# 4AND_1.net
KiCad netlist of a schematic drawn in EAGLE
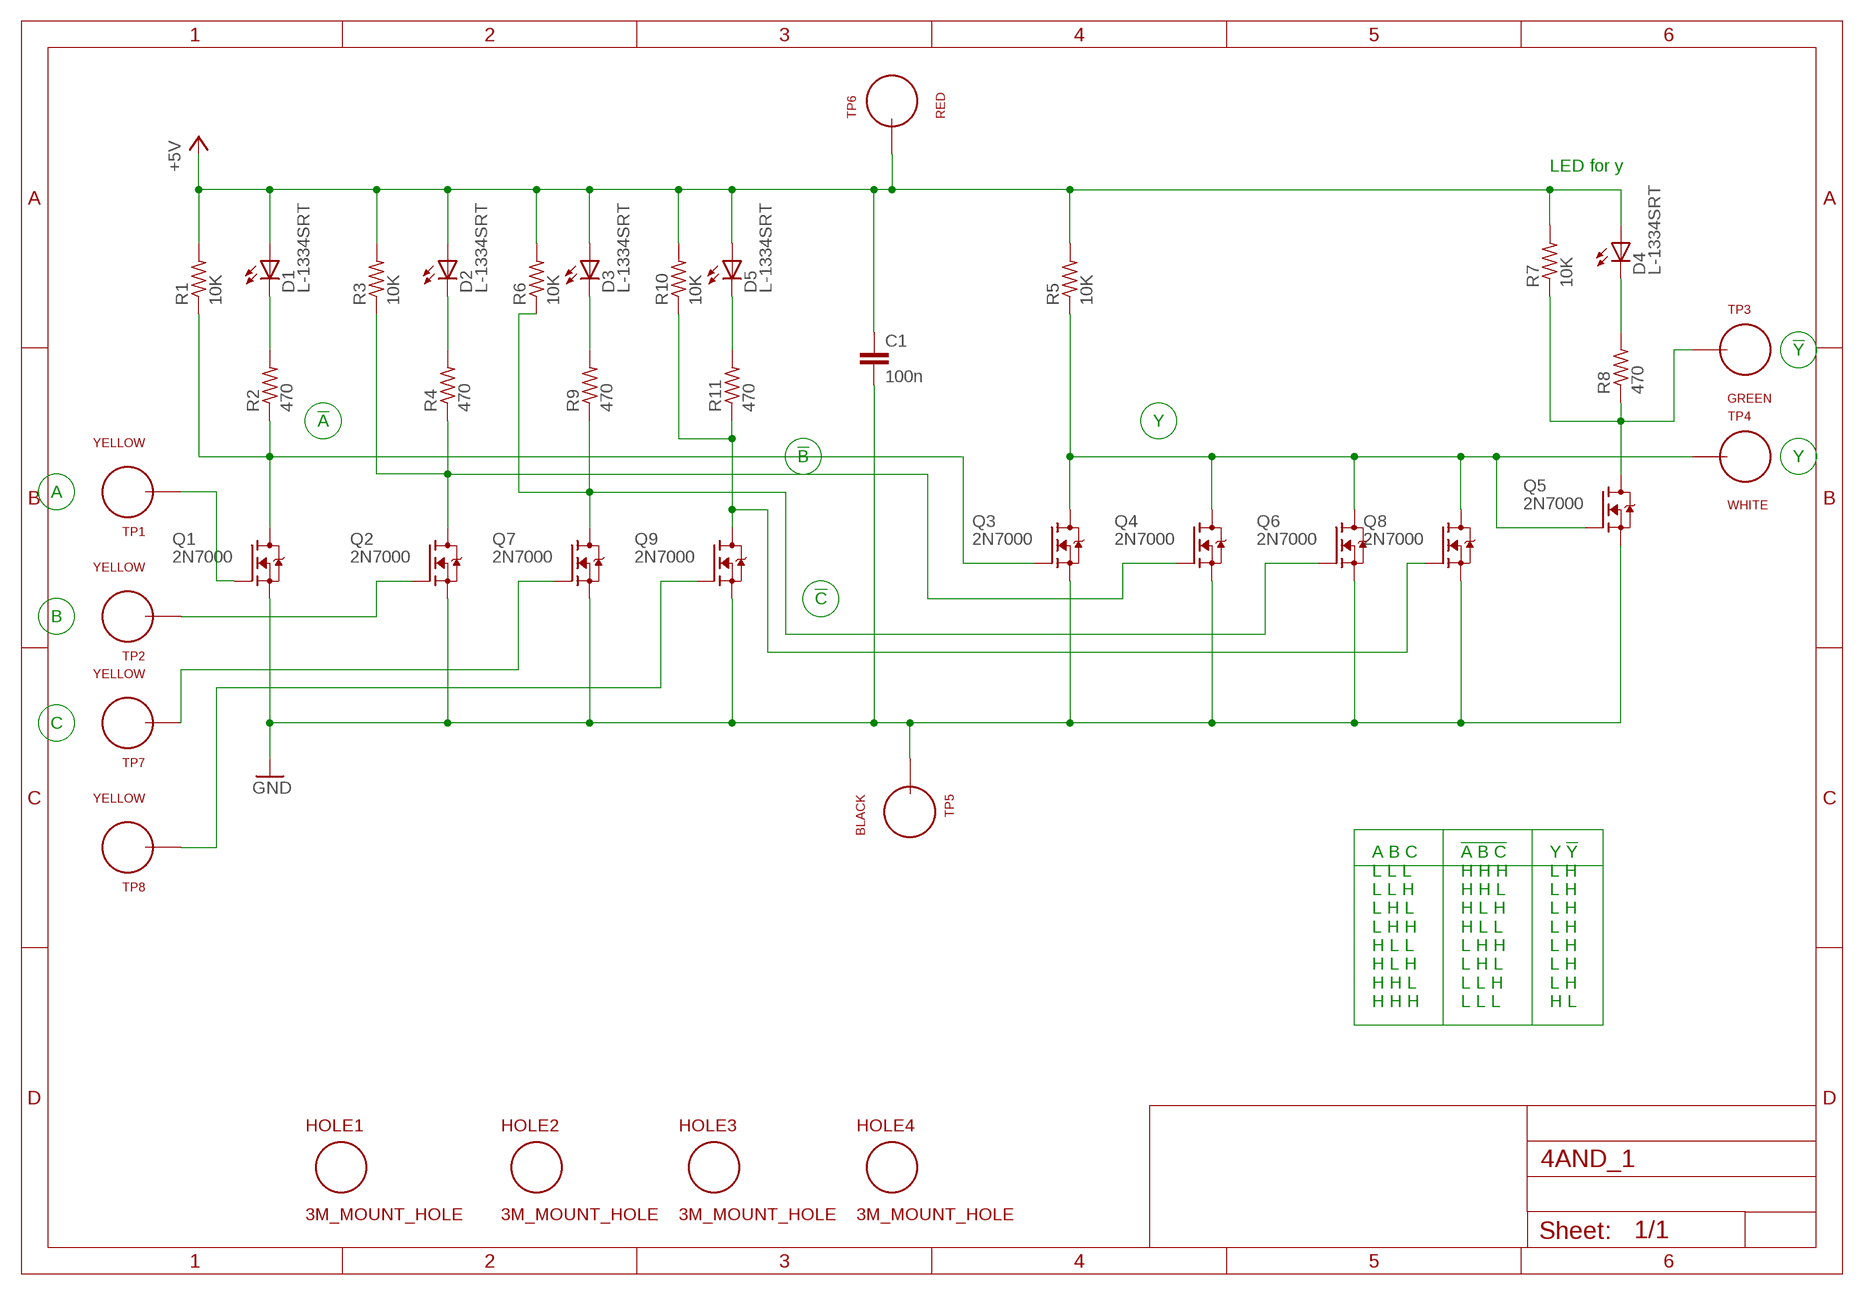
[diagram p0: schematic, sheet 1]

(export (version "E")
  (design (tool "Eeschema 10.0.6"))
  (components
    (comp (ref "C1")
      (value "100n")
      (footprint "eagle-import:CAP_P2INCH")
      (libsource (lib "eagle-import") (part "C_P2INCH"))
    )
    (comp (ref "D1")
      (value "L-1334SRT")
      (footprint "eagle-import:LED3MM")
      (libsource (lib "eagle-import") (part "L-1334SRT"))
    )
    (comp (ref "D2")
      (value "L-1334SRT")
      (footprint "eagle-import:LED3MM")
      (libsource (lib "eagle-import") (part "L-1334SRT"))
    )
    (comp (ref "D3")
      (value "L-1334SRT")
      (footprint "eagle-import:LED3MM")
      (libsource (lib "eagle-import") (part "L-1334SRT"))
    )
    (comp (ref "D4")
      (value "L-1334SRT")
      (footprint "eagle-import:LED3MM")
      (libsource (lib "eagle-import") (part "L-1334SRT"))
    )
    (comp (ref "D5")
      (value "L-1334SRT")
      (footprint "eagle-import:LED3MM")
      (libsource (lib "eagle-import") (part "L-1334SRT"))
    )
    (comp (ref "HOLE1")
      (value "3M_MOUNT_HOLE")
      (footprint "eagle-import:3M_HOLE")
      (libsource (lib "eagle-import") (part "3M_MOUNT_HOLE"))
    )
    (comp (ref "HOLE2")
      (value "3M_MOUNT_HOLE")
      (footprint "eagle-import:3M_HOLE")
      (libsource (lib "eagle-import") (part "3M_MOUNT_HOLE"))
    )
    (comp (ref "HOLE3")
      (value "3M_MOUNT_HOLE")
      (footprint "eagle-import:3M_HOLE")
      (libsource (lib "eagle-import") (part "3M_MOUNT_HOLE"))
    )
    (comp (ref "HOLE4")
      (value "3M_MOUNT_HOLE")
      (footprint "eagle-import:3M_HOLE")
      (libsource (lib "eagle-import") (part "3M_MOUNT_HOLE"))
    )
    (comp (ref "Q1")
      (value "2N7000")
      (footprint "eagle-import:TO92-DGS")
      (libsource (lib "eagle-import") (part "2N7000"))
    )
    (comp (ref "Q2")
      (value "2N7000")
      (footprint "eagle-import:TO92-DGS")
      (libsource (lib "eagle-import") (part "2N7000"))
    )
    (comp (ref "Q3")
      (value "2N7000")
      (footprint "eagle-import:TO92-DGS")
      (libsource (lib "eagle-import") (part "2N7000"))
    )
    (comp (ref "Q4")
      (value "2N7000")
      (footprint "eagle-import:TO92-DGS")
      (libsource (lib "eagle-import") (part "2N7000"))
    )
    (comp (ref "Q5")
      (value "2N7000")
      (footprint "eagle-import:TO92-DGS")
      (libsource (lib "eagle-import") (part "2N7000"))
    )
    (comp (ref "Q6")
      (value "2N7000")
      (footprint "eagle-import:TO92-DGS")
      (libsource (lib "eagle-import") (part "2N7000"))
    )
    (comp (ref "Q7")
      (value "2N7000")
      (footprint "eagle-import:TO92-DGS")
      (libsource (lib "eagle-import") (part "2N7000"))
    )
    (comp (ref "Q8")
      (value "2N7000")
      (footprint "eagle-import:TO92-DGS")
      (libsource (lib "eagle-import") (part "2N7000"))
    )
    (comp (ref "Q9")
      (value "2N7000")
      (footprint "eagle-import:TO92-DGS")
      (libsource (lib "eagle-import") (part "2N7000"))
    )
    (comp (ref "R1")
      (value "10K")
      (footprint "eagle-import:R_P2INCH")
      (libsource (lib "eagle-import") (part "R_P2INCH"))
    )
    (comp (ref "R2")
      (value "470")
      (footprint "eagle-import:R_P2INCH")
      (libsource (lib "eagle-import") (part "R_P2INCH"))
    )
    (comp (ref "R3")
      (value "10K")
      (footprint "eagle-import:R_P2INCH")
      (libsource (lib "eagle-import") (part "R_P2INCH"))
    )
    (comp (ref "R4")
      (value "470")
      (footprint "eagle-import:R_P2INCH")
      (libsource (lib "eagle-import") (part "R_P2INCH"))
    )
    (comp (ref "R5")
      (value "10K")
      (footprint "eagle-import:R_P2INCH")
      (libsource (lib "eagle-import") (part "R_P2INCH"))
    )
    (comp (ref "R6")
      (value "10K")
      (footprint "eagle-import:R_P2INCH")
      (libsource (lib "eagle-import") (part "R_P2INCH"))
    )
    (comp (ref "R7")
      (value "10K")
      (footprint "eagle-import:R_P2INCH")
      (libsource (lib "eagle-import") (part "R_P2INCH"))
    )
    (comp (ref "R8")
      (value "470")
      (footprint "eagle-import:R_P2INCH")
      (libsource (lib "eagle-import") (part "R_P2INCH"))
    )
    (comp (ref "R9")
      (value "470")
      (footprint "eagle-import:R_P2INCH")
      (libsource (lib "eagle-import") (part "R_P2INCH"))
    )
    (comp (ref "R10")
      (value "10K")
      (footprint "eagle-import:R_P2INCH")
      (libsource (lib "eagle-import") (part "R_P2INCH"))
    )
    (comp (ref "R11")
      (value "470")
      (footprint "eagle-import:R_P2INCH")
      (libsource (lib "eagle-import") (part "R_P2INCH"))
    )
    (comp (ref "TP1")
      (value "YELLOW")
      (footprint "eagle-import:TEST_LOOP")
      (libsource (lib "eagle-import") (part "TEST_LOOP"))
    )
    (comp (ref "TP2")
      (value "YELLOW")
      (footprint "eagle-import:TEST_LOOP")
      (libsource (lib "eagle-import") (part "TEST_LOOP"))
    )
    (comp (ref "TP3")
      (value "GREEN")
      (footprint "eagle-import:TEST_LOOP")
      (libsource (lib "eagle-import") (part "TEST_LOOP"))
    )
    (comp (ref "TP4")
      (value "WHITE")
      (footprint "eagle-import:TEST_LOOP")
      (libsource (lib "eagle-import") (part "TEST_LOOP"))
    )
    (comp (ref "TP5")
      (value "BLACK")
      (footprint "eagle-import:TEST_LOOP")
      (libsource (lib "eagle-import") (part "TEST_LOOP"))
    )
    (comp (ref "TP6")
      (value "RED")
      (footprint "eagle-import:TEST_LOOP")
      (libsource (lib "eagle-import") (part "TEST_LOOP"))
    )
    (comp (ref "TP7")
      (value "YELLOW")
      (footprint "eagle-import:TEST_LOOP")
      (libsource (lib "eagle-import") (part "TEST_LOOP"))
    )
    (comp (ref "TP8")
      (value "YELLOW")
      (footprint "eagle-import:TEST_LOOP")
      (libsource (lib "eagle-import") (part "TEST_LOOP"))
    )
  )
  (nets
    (net (code "1") (name "+5V") (class "Default")
      (node (ref "C1") (pin "1") (pinfunction "1_1") (pintype "passive"))
      (node (ref "D1") (pin "A") (pinfunction "A_A") (pintype "passive"))
      (node (ref "D2") (pin "A") (pinfunction "A_A") (pintype "passive"))
      (node (ref "D3") (pin "A") (pinfunction "A_A") (pintype "passive"))
      (node (ref "D4") (pin "A") (pinfunction "A_A") (pintype "passive"))
      (node (ref "D5") (pin "A") (pinfunction "A_A") (pintype "passive"))
      (node (ref "R1") (pin "2") (pinfunction "2_2") (pintype "passive"))
      (node (ref "R10") (pin "2") (pinfunction "2_2") (pintype "passive"))
      (node (ref "R3") (pin "2") (pinfunction "2_2") (pintype "passive"))
      (node (ref "R5") (pin "2") (pinfunction "2_2") (pintype "passive"))
      (node (ref "R6") (pin "2") (pinfunction "2_2") (pintype "passive"))
      (node (ref "R7") (pin "2") (pinfunction "2_2") (pintype "passive"))
      (node (ref "TP6") (pin "P$1") (pinfunction "P$1_P$1") (pintype "bidirectional"))
    )
    (net (code "2") (name "GND") (class "Default")
      (node (ref "C1") (pin "2") (pinfunction "2_2") (pintype "passive"))
      (node (ref "Q1") (pin "S") (pinfunction "S_S") (pintype "passive"))
      (node (ref "Q2") (pin "S") (pinfunction "S_S") (pintype "passive"))
      (node (ref "Q3") (pin "S") (pinfunction "S_S") (pintype "passive"))
      (node (ref "Q4") (pin "S") (pinfunction "S_S") (pintype "passive"))
      (node (ref "Q5") (pin "S") (pinfunction "S_S") (pintype "passive"))
      (node (ref "Q6") (pin "S") (pinfunction "S_S") (pintype "passive"))
      (node (ref "Q7") (pin "S") (pinfunction "S_S") (pintype "passive"))
      (node (ref "Q8") (pin "S") (pinfunction "S_S") (pintype "passive"))
      (node (ref "Q9") (pin "S") (pinfunction "S_S") (pintype "passive"))
      (node (ref "TP5") (pin "P$1") (pinfunction "P$1_P$1") (pintype "bidirectional"))
    )
    (net (code "3") (name "Net-(D1-C)") (class "Default")
      (node (ref "D1") (pin "K") (pinfunction "C_K") (pintype "passive"))
      (node (ref "R2") (pin "2") (pinfunction "2_2") (pintype "passive"))
    )
    (net (code "4") (name "Net-(D2-C)") (class "Default")
      (node (ref "D2") (pin "K") (pinfunction "C_K") (pintype "passive"))
      (node (ref "R4") (pin "2") (pinfunction "2_2") (pintype "passive"))
    )
    (net (code "5") (name "Net-(D3-C)") (class "Default")
      (node (ref "D3") (pin "K") (pinfunction "C_K") (pintype "passive"))
      (node (ref "R9") (pin "2") (pinfunction "2_2") (pintype "passive"))
    )
    (net (code "6") (name "Net-(D4-C)") (class "Default")
      (node (ref "D4") (pin "K") (pinfunction "C_K") (pintype "passive"))
      (node (ref "R8") (pin "2") (pinfunction "2_2") (pintype "passive"))
    )
    (net (code "7") (name "Net-(D5-C)") (class "Default")
      (node (ref "D5") (pin "K") (pinfunction "C_K") (pintype "passive"))
      (node (ref "R11") (pin "2") (pinfunction "2_2") (pintype "passive"))
    )
    (net (code "8") (name "Net-(Q1-PadD)") (class "Default")
      (node (ref "Q1") (pin "D") (pinfunction "D_D") (pintype "passive"))
      (node (ref "Q3") (pin "G") (pinfunction "G_G") (pintype "passive"))
      (node (ref "R1") (pin "1") (pinfunction "1_1") (pintype "passive"))
      (node (ref "R2") (pin "1") (pinfunction "1_1") (pintype "passive"))
    )
    (net (code "9") (name "Net-(Q1-PadG)") (class "Default")
      (node (ref "Q1") (pin "G") (pinfunction "G_G") (pintype "passive"))
      (node (ref "TP1") (pin "P$1") (pinfunction "P$1_P$1") (pintype "bidirectional"))
    )
    (net (code "10") (name "Net-(Q2-PadD)") (class "Default")
      (node (ref "Q2") (pin "D") (pinfunction "D_D") (pintype "passive"))
      (node (ref "Q4") (pin "G") (pinfunction "G_G") (pintype "passive"))
      (node (ref "R3") (pin "1") (pinfunction "1_1") (pintype "passive"))
      (node (ref "R4") (pin "1") (pinfunction "1_1") (pintype "passive"))
    )
    (net (code "11") (name "Net-(Q2-PadG)") (class "Default")
      (node (ref "Q2") (pin "G") (pinfunction "G_G") (pintype "passive"))
      (node (ref "TP2") (pin "P$1") (pinfunction "P$1_P$1") (pintype "bidirectional"))
    )
    (net (code "12") (name "Net-(Q3-PadD)") (class "Default")
      (node (ref "Q3") (pin "D") (pinfunction "D_D") (pintype "passive"))
      (node (ref "Q4") (pin "D") (pinfunction "D_D") (pintype "passive"))
      (node (ref "Q5") (pin "G") (pinfunction "G_G") (pintype "passive"))
      (node (ref "Q6") (pin "D") (pinfunction "D_D") (pintype "passive"))
      (node (ref "Q8") (pin "D") (pinfunction "D_D") (pintype "passive"))
      (node (ref "R5") (pin "1") (pinfunction "1_1") (pintype "passive"))
      (node (ref "TP4") (pin "P$1") (pinfunction "P$1_P$1") (pintype "bidirectional"))
    )
    (net (code "13") (name "Net-(Q5-PadD)") (class "Default")
      (node (ref "Q5") (pin "D") (pinfunction "D_D") (pintype "passive"))
      (node (ref "R7") (pin "1") (pinfunction "1_1") (pintype "passive"))
      (node (ref "R8") (pin "1") (pinfunction "1_1") (pintype "passive"))
      (node (ref "TP3") (pin "P$1") (pinfunction "P$1_P$1") (pintype "bidirectional"))
    )
    (net (code "14") (name "Net-(Q6-PadG)") (class "Default")
      (node (ref "Q6") (pin "G") (pinfunction "G_G") (pintype "passive"))
      (node (ref "Q7") (pin "D") (pinfunction "D_D") (pintype "passive"))
      (node (ref "R6") (pin "1") (pinfunction "1_1") (pintype "passive"))
      (node (ref "R9") (pin "1") (pinfunction "1_1") (pintype "passive"))
    )
    (net (code "15") (name "Net-(Q7-PadG)") (class "Default")
      (node (ref "Q7") (pin "G") (pinfunction "G_G") (pintype "passive"))
      (node (ref "TP7") (pin "P$1") (pinfunction "P$1_P$1") (pintype "bidirectional"))
    )
    (net (code "16") (name "Net-(Q8-PadG)") (class "Default")
      (node (ref "Q8") (pin "G") (pinfunction "G_G") (pintype "passive"))
      (node (ref "Q9") (pin "D") (pinfunction "D_D") (pintype "passive"))
      (node (ref "R10") (pin "1") (pinfunction "1_1") (pintype "passive"))
      (node (ref "R11") (pin "1") (pinfunction "1_1") (pintype "passive"))
    )
    (net (code "17") (name "Net-(Q9-PadG)") (class "Default")
      (node (ref "Q9") (pin "G") (pinfunction "G_G") (pintype "passive"))
      (node (ref "TP8") (pin "P$1") (pinfunction "P$1_P$1") (pintype "bidirectional"))
    )
  )
)
